# GC.net
KiCad netlist of a schematic drawn in EAGLE
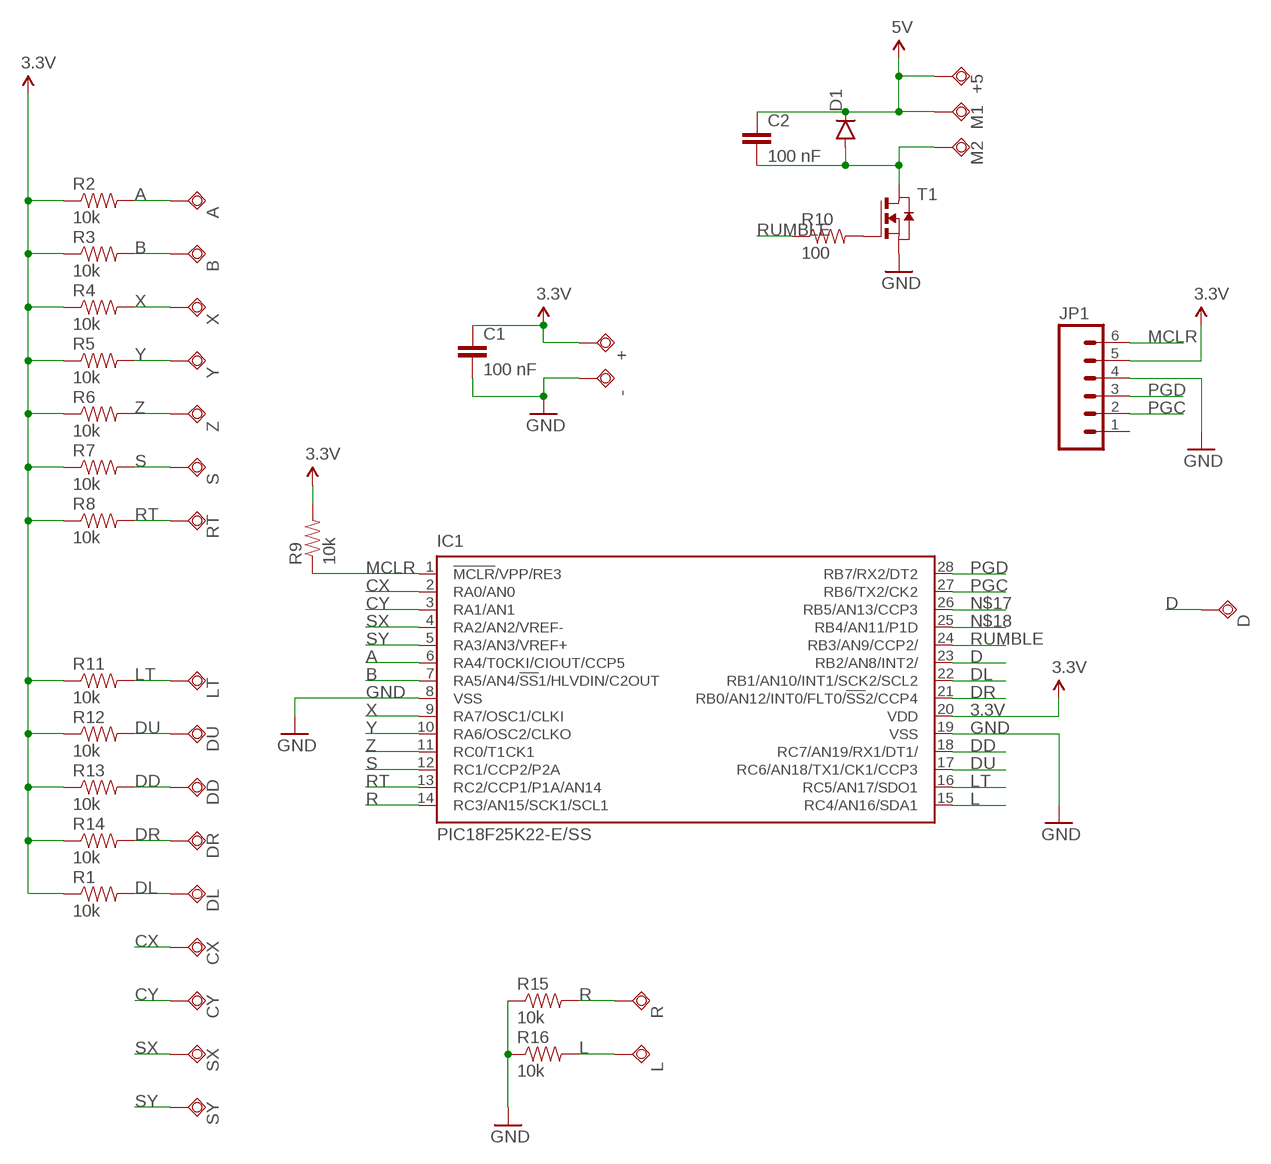
[diagram p0: schematic, sheet 1]

(export (version "E")
  (design (tool "Eeschema 10.0.6"))
  (components
    (comp (ref "+")
      (value "TPSQTP10SQ")
      (footprint "eagle-import:TP10SQ")
      (libsource (lib "eagle-import") (part "TPSQTP10SQ"))
    )
    (comp (ref "+5")
      (value "TPSQTP10SQ")
      (footprint "eagle-import:TP10SQ")
      (libsource (lib "eagle-import") (part "TPSQTP10SQ"))
    )
    (comp (ref "-")
      (value "TPSQTP10SQ")
      (footprint "eagle-import:TP10SQ")
      (libsource (lib "eagle-import") (part "TPSQTP10SQ"))
    )
    (comp (ref "A")
      (value "TPSQTP10SQ")
      (footprint "eagle-import:TP10SQ")
      (libsource (lib "eagle-import") (part "TPSQTP10SQ"))
    )
    (comp (ref "B")
      (value "TPSQTP10SQ")
      (footprint "eagle-import:TP10SQ")
      (libsource (lib "eagle-import") (part "TPSQTP10SQ"))
    )
    (comp (ref "C1")
      (value "100 nF")
      (footprint "eagle-import:0805")
      (libsource (lib "eagle-import") (part "CAP0805"))
    )
    (comp (ref "C2")
      (value "100 nF")
      (footprint "eagle-import:0805")
      (libsource (lib "eagle-import") (part "CAP0805"))
    )
    (comp (ref "CX")
      (value "TPSQTP10SQ")
      (footprint "eagle-import:TP10SQ")
      (libsource (lib "eagle-import") (part "TPSQTP10SQ"))
    )
    (comp (ref "CY")
      (value "TPSQTP10SQ")
      (footprint "eagle-import:TP10SQ")
      (libsource (lib "eagle-import") (part "TPSQTP10SQ"))
    )
    (comp (ref "D")
      (value "TPSQTP10SQ")
      (footprint "eagle-import:TP10SQ")
      (libsource (lib "eagle-import") (part "TPSQTP10SQ"))
    )
    (comp (ref "D1")
      (value "DIODEBAS16")
      (footprint "eagle-import:SOD-323")
      (libsource (lib "eagle-import") (part "DIODEBAS16"))
    )
    (comp (ref "DD")
      (value "TPSQTP10SQ")
      (footprint "eagle-import:TP10SQ")
      (libsource (lib "eagle-import") (part "TPSQTP10SQ"))
    )
    (comp (ref "DL")
      (value "TPSQTP10SQ")
      (footprint "eagle-import:TP10SQ")
      (libsource (lib "eagle-import") (part "TPSQTP10SQ"))
    )
    (comp (ref "DR")
      (value "TPSQTP10SQ")
      (footprint "eagle-import:TP10SQ")
      (libsource (lib "eagle-import") (part "TPSQTP10SQ"))
    )
    (comp (ref "DU")
      (value "TPSQTP10SQ")
      (footprint "eagle-import:TP10SQ")
      (libsource (lib "eagle-import") (part "TPSQTP10SQ"))
    )
    (comp (ref "IC1")
      (value "PIC18F25K22-E/SS")
      (footprint "eagle-import:SSOP28")
      (libsource (lib "eagle-import") (part "PIC18F25K22/SS-E"))
    )
    (comp (ref "JP1")
      (value "M06SILK_FEMALE_PTH")
      (footprint "eagle-import:1X06")
      (libsource (lib "eagle-import") (part "M06SILK_FEMALE_PTH"))
    )
    (comp (ref "L")
      (value "TPSQTP10SQ")
      (footprint "eagle-import:TP10SQ")
      (libsource (lib "eagle-import") (part "TPSQTP10SQ"))
    )
    (comp (ref "LT")
      (value "TPSQTP10SQ")
      (footprint "eagle-import:TP10SQ")
      (libsource (lib "eagle-import") (part "TPSQTP10SQ"))
    )
    (comp (ref "M1")
      (value "TPSQTP10SQ")
      (footprint "eagle-import:TP10SQ")
      (libsource (lib "eagle-import") (part "TPSQTP10SQ"))
    )
    (comp (ref "M2")
      (value "TPSQTP10SQ")
      (footprint "eagle-import:TP10SQ")
      (libsource (lib "eagle-import") (part "TPSQTP10SQ"))
    )
    (comp (ref "R")
      (value "TPSQTP10SQ")
      (footprint "eagle-import:TP10SQ")
      (libsource (lib "eagle-import") (part "TPSQTP10SQ"))
    )
    (comp (ref "R1")
      (value "10k")
      (footprint "eagle-import:0805")
      (libsource (lib "eagle-import") (part "RESISTOR0805-RES"))
    )
    (comp (ref "R2")
      (value "10k")
      (footprint "eagle-import:0805")
      (libsource (lib "eagle-import") (part "RESISTOR0805-RES"))
    )
    (comp (ref "R3")
      (value "10k")
      (footprint "eagle-import:0805")
      (libsource (lib "eagle-import") (part "RESISTOR0805-RES"))
    )
    (comp (ref "R4")
      (value "10k")
      (footprint "eagle-import:0805")
      (libsource (lib "eagle-import") (part "RESISTOR0805-RES"))
    )
    (comp (ref "R5")
      (value "10k")
      (footprint "eagle-import:0805")
      (libsource (lib "eagle-import") (part "RESISTOR0805-RES"))
    )
    (comp (ref "R6")
      (value "10k")
      (footprint "eagle-import:0805")
      (libsource (lib "eagle-import") (part "RESISTOR0805-RES"))
    )
    (comp (ref "R7")
      (value "10k")
      (footprint "eagle-import:0805")
      (libsource (lib "eagle-import") (part "RESISTOR0805-RES"))
    )
    (comp (ref "R8")
      (value "10k")
      (footprint "eagle-import:0805")
      (libsource (lib "eagle-import") (part "RESISTOR0805-RES"))
    )
    (comp (ref "R9")
      (value "10k")
      (footprint "eagle-import:0805")
      (libsource (lib "eagle-import") (part "RESISTOR0805-RES"))
    )
    (comp (ref "R10")
      (value "100")
      (footprint "eagle-import:0805")
      (libsource (lib "eagle-import") (part "RESISTOR0805-RES"))
    )
    (comp (ref "R11")
      (value "10k")
      (footprint "eagle-import:0805")
      (libsource (lib "eagle-import") (part "RESISTOR0805-RES"))
    )
    (comp (ref "R12")
      (value "10k")
      (footprint "eagle-import:0805")
      (libsource (lib "eagle-import") (part "RESISTOR0805-RES"))
    )
    (comp (ref "R13")
      (value "10k")
      (footprint "eagle-import:0805")
      (libsource (lib "eagle-import") (part "RESISTOR0805-RES"))
    )
    (comp (ref "R14")
      (value "10k")
      (footprint "eagle-import:0805")
      (libsource (lib "eagle-import") (part "RESISTOR0805-RES"))
    )
    (comp (ref "R15")
      (value "10k")
      (footprint "eagle-import:0805")
      (libsource (lib "eagle-import") (part "RESISTOR0805-RES"))
    )
    (comp (ref "R16")
      (value "10k")
      (footprint "eagle-import:0805")
      (libsource (lib "eagle-import") (part "RESISTOR0805-RES"))
    )
    (comp (ref "RT")
      (value "TPSQTP10SQ")
      (footprint "eagle-import:TP10SQ")
      (libsource (lib "eagle-import") (part "TPSQTP10SQ"))
    )
    (comp (ref "S")
      (value "TPSQTP10SQ")
      (footprint "eagle-import:TP10SQ")
      (libsource (lib "eagle-import") (part "TPSQTP10SQ"))
    )
    (comp (ref "SX")
      (value "TPSQTP10SQ")
      (footprint "eagle-import:TP10SQ")
      (libsource (lib "eagle-import") (part "TPSQTP10SQ"))
    )
    (comp (ref "SY")
      (value "TPSQTP10SQ")
      (footprint "eagle-import:TP10SQ")
      (libsource (lib "eagle-import") (part "TPSQTP10SQ"))
    )
    (comp (ref "T1")
      (value "NMOSSOT23")
      (footprint "eagle-import:SOT-23")
      (libsource (lib "eagle-import") (part "NMOSSOT23"))
    )
    (comp (ref "X")
      (value "TPSQTP10SQ")
      (footprint "eagle-import:TP10SQ")
      (libsource (lib "eagle-import") (part "TPSQTP10SQ"))
    )
    (comp (ref "Y")
      (value "TPSQTP10SQ")
      (footprint "eagle-import:TP10SQ")
      (libsource (lib "eagle-import") (part "TPSQTP10SQ"))
    )
    (comp (ref "Z")
      (value "TPSQTP10SQ")
      (footprint "eagle-import:TP10SQ")
      (libsource (lib "eagle-import") (part "TPSQTP10SQ"))
    )
  )
  (nets
    (net (code "1") (name "/A") (class "Default")
      (node (ref "A") (pin "TP") (pinfunction "TP_TP") (pintype "input"))
      (node (ref "IC1") (pin "6") (pinfunction "RA4/T0CKI/CIOUT/CCP5_6") (pintype "bidirectional"))
      (node (ref "R2") (pin "2") (pinfunction "2_2") (pintype "passive"))
    )
    (net (code "2") (name "/B") (class "Default")
      (node (ref "B") (pin "TP") (pinfunction "TP_TP") (pintype "input"))
      (node (ref "IC1") (pin "7") (pinfunction "RA5/AN4/~{SS}1/HLVDIN/C2OUT_7") (pintype "bidirectional"))
      (node (ref "R3") (pin "2") (pinfunction "2_2") (pintype "passive"))
    )
    (net (code "3") (name "/CX") (class "Default")
      (node (ref "CX") (pin "TP") (pinfunction "TP_TP") (pintype "input"))
      (node (ref "IC1") (pin "2") (pinfunction "RA0/AN0_2") (pintype "bidirectional"))
    )
    (net (code "4") (name "/CY") (class "Default")
      (node (ref "CY") (pin "TP") (pinfunction "TP_TP") (pintype "input"))
      (node (ref "IC1") (pin "3") (pinfunction "RA1/AN1_3") (pintype "bidirectional"))
    )
    (net (code "5") (name "/D") (class "Default")
      (node (ref "D") (pin "TP") (pinfunction "TP_TP") (pintype "input"))
      (node (ref "IC1") (pin "23") (pinfunction "RB2/AN8/INT2/_23") (pintype "bidirectional"))
    )
    (net (code "6") (name "/DD") (class "Default")
      (node (ref "DD") (pin "TP") (pinfunction "TP_TP") (pintype "input"))
      (node (ref "IC1") (pin "18") (pinfunction "RC7/AN19/RX1/DT1/_18") (pintype "bidirectional"))
      (node (ref "R13") (pin "2") (pinfunction "2_2") (pintype "passive"))
    )
    (net (code "7") (name "/DL") (class "Default")
      (node (ref "DL") (pin "TP") (pinfunction "TP_TP") (pintype "input"))
      (node (ref "IC1") (pin "22") (pinfunction "RB1/AN10/INT1/SCK2/SCL2_22") (pintype "bidirectional"))
      (node (ref "R1") (pin "2") (pinfunction "2_2") (pintype "passive"))
    )
    (net (code "8") (name "/DR") (class "Default")
      (node (ref "DR") (pin "TP") (pinfunction "TP_TP") (pintype "input"))
      (node (ref "IC1") (pin "21") (pinfunction "RB0/AN12/INT0/FLT0/~{SS}2/CCP4_21") (pintype "bidirectional"))
      (node (ref "R14") (pin "2") (pinfunction "2_2") (pintype "passive"))
    )
    (net (code "9") (name "/DU") (class "Default")
      (node (ref "DU") (pin "TP") (pinfunction "TP_TP") (pintype "input"))
      (node (ref "IC1") (pin "17") (pinfunction "RC6/AN18/TX1/CK1/CCP3_17") (pintype "bidirectional"))
      (node (ref "R12") (pin "2") (pinfunction "2_2") (pintype "passive"))
    )
    (net (code "10") (name "/L") (class "Default")
      (node (ref "IC1") (pin "15") (pinfunction "RC4/AN16/SDA1_15") (pintype "bidirectional"))
      (node (ref "L") (pin "TP") (pinfunction "TP_TP") (pintype "input"))
      (node (ref "R16") (pin "2") (pinfunction "2_2") (pintype "passive"))
    )
    (net (code "11") (name "/LT") (class "Default")
      (node (ref "IC1") (pin "16") (pinfunction "RC5/AN17/SDO1_16") (pintype "bidirectional"))
      (node (ref "LT") (pin "TP") (pinfunction "TP_TP") (pintype "input"))
      (node (ref "R11") (pin "2") (pinfunction "2_2") (pintype "passive"))
    )
    (net (code "12") (name "/MCLR") (class "Default")
      (node (ref "IC1") (pin "1") (pinfunction "~{MCLR}/VPP/RE3_1") (pintype "input"))
      (node (ref "JP1") (pin "6") (pinfunction "6_6") (pintype "passive"))
      (node (ref "R9") (pin "1") (pinfunction "1_1") (pintype "passive"))
    )
    (net (code "13") (name "/N$17") (class "Default")
      (node (ref "IC1") (pin "26") (pinfunction "RB5/AN13/CCP3_26") (pintype "bidirectional"))
    )
    (net (code "14") (name "/N$18") (class "Default")
      (node (ref "IC1") (pin "25") (pinfunction "RB4/AN11/P1D_25") (pintype "bidirectional"))
    )
    (net (code "15") (name "/PGC") (class "Default")
      (node (ref "IC1") (pin "27") (pinfunction "RB6/TX2/CK2_27") (pintype "bidirectional"))
      (node (ref "JP1") (pin "2") (pinfunction "2_2") (pintype "passive"))
    )
    (net (code "16") (name "/PGD") (class "Default")
      (node (ref "IC1") (pin "28") (pinfunction "RB7/RX2/DT2_28") (pintype "bidirectional"))
      (node (ref "JP1") (pin "3") (pinfunction "3_3") (pintype "passive"))
    )
    (net (code "17") (name "/R") (class "Default")
      (node (ref "IC1") (pin "14") (pinfunction "RC3/AN15/SCK1/SCL1_14") (pintype "bidirectional"))
      (node (ref "R") (pin "TP") (pinfunction "TP_TP") (pintype "input"))
      (node (ref "R15") (pin "2") (pinfunction "2_2") (pintype "passive"))
    )
    (net (code "18") (name "/RT") (class "Default")
      (node (ref "IC1") (pin "13") (pinfunction "RC2/CCP1/P1A/AN14_13") (pintype "bidirectional"))
      (node (ref "R8") (pin "2") (pinfunction "2_2") (pintype "passive"))
      (node (ref "RT") (pin "TP") (pinfunction "TP_TP") (pintype "input"))
    )
    (net (code "19") (name "/RUMBLE") (class "Default")
      (node (ref "IC1") (pin "24") (pinfunction "RB3/AN9/CCP2/_24") (pintype "bidirectional"))
      (node (ref "R10") (pin "1") (pinfunction "1_1") (pintype "passive"))
    )
    (net (code "20") (name "/S") (class "Default")
      (node (ref "IC1") (pin "12") (pinfunction "RC1/CCP2/P2A_12") (pintype "bidirectional"))
      (node (ref "R7") (pin "2") (pinfunction "2_2") (pintype "passive"))
      (node (ref "S") (pin "TP") (pinfunction "TP_TP") (pintype "input"))
    )
    (net (code "21") (name "/SX") (class "Default")
      (node (ref "IC1") (pin "4") (pinfunction "RA2/AN2/VREF-_4") (pintype "bidirectional"))
      (node (ref "SX") (pin "TP") (pinfunction "TP_TP") (pintype "input"))
    )
    (net (code "22") (name "/SY") (class "Default")
      (node (ref "IC1") (pin "5") (pinfunction "RA3/AN3/VREF+_5") (pintype "bidirectional"))
      (node (ref "SY") (pin "TP") (pinfunction "TP_TP") (pintype "input"))
    )
    (net (code "23") (name "/X") (class "Default")
      (node (ref "IC1") (pin "9") (pinfunction "RA7/OSC1/CLKI_9") (pintype "input"))
      (node (ref "R4") (pin "2") (pinfunction "2_2") (pintype "passive"))
      (node (ref "X") (pin "TP") (pinfunction "TP_TP") (pintype "input"))
    )
    (net (code "24") (name "/Y") (class "Default")
      (node (ref "IC1") (pin "10") (pinfunction "RA6/OSC2/CLKO_10") (pintype "output"))
      (node (ref "R5") (pin "2") (pinfunction "2_2") (pintype "passive"))
      (node (ref "Y") (pin "TP") (pinfunction "TP_TP") (pintype "input"))
    )
    (net (code "25") (name "/Z") (class "Default")
      (node (ref "IC1") (pin "11") (pinfunction "RC0/T1CK1_11") (pintype "bidirectional"))
      (node (ref "R6") (pin "2") (pinfunction "2_2") (pintype "passive"))
      (node (ref "Z") (pin "TP") (pinfunction "TP_TP") (pintype "input"))
    )
    (net (code "26") (name "3.3V") (class "Default")
      (node (ref "+") (pin "TP") (pinfunction "TP_TP") (pintype "input"))
      (node (ref "C1") (pin "1") (pinfunction "1_1") (pintype "passive"))
      (node (ref "IC1") (pin "20") (pinfunction "VDD_20") (pintype "power_in"))
      (node (ref "JP1") (pin "5") (pinfunction "5_5") (pintype "passive"))
      (node (ref "R1") (pin "1") (pinfunction "1_1") (pintype "passive"))
      (node (ref "R11") (pin "1") (pinfunction "1_1") (pintype "passive"))
      (node (ref "R12") (pin "1") (pinfunction "1_1") (pintype "passive"))
      (node (ref "R13") (pin "1") (pinfunction "1_1") (pintype "passive"))
      (node (ref "R14") (pin "1") (pinfunction "1_1") (pintype "passive"))
      (node (ref "R2") (pin "1") (pinfunction "1_1") (pintype "passive"))
      (node (ref "R3") (pin "1") (pinfunction "1_1") (pintype "passive"))
      (node (ref "R4") (pin "1") (pinfunction "1_1") (pintype "passive"))
      (node (ref "R5") (pin "1") (pinfunction "1_1") (pintype "passive"))
      (node (ref "R6") (pin "1") (pinfunction "1_1") (pintype "passive"))
      (node (ref "R7") (pin "1") (pinfunction "1_1") (pintype "passive"))
      (node (ref "R8") (pin "1") (pinfunction "1_1") (pintype "passive"))
      (node (ref "R9") (pin "2") (pinfunction "2_2") (pintype "passive"))
    )
    (net (code "27") (name "5V") (class "Default")
      (node (ref "+5") (pin "TP") (pinfunction "TP_TP") (pintype "input"))
      (node (ref "C2") (pin "1") (pinfunction "1_1") (pintype "passive"))
      (node (ref "D1") (pin "C") (pinfunction "C_C") (pintype "passive"))
      (node (ref "M1") (pin "TP") (pinfunction "TP_TP") (pintype "input"))
    )
    (net (code "28") (name "GND") (class "Default")
      (node (ref "-") (pin "TP") (pinfunction "TP_TP") (pintype "input"))
      (node (ref "C1") (pin "2") (pinfunction "2_2") (pintype "passive"))
      (node (ref "IC1") (pin "19") (pinfunction "VSS_19") (pintype "power_in"))
      (node (ref "IC1") (pin "8") (pinfunction "VSS_8") (pintype "power_in"))
      (node (ref "JP1") (pin "4") (pinfunction "4_4") (pintype "passive"))
      (node (ref "R15") (pin "1") (pinfunction "1_1") (pintype "passive"))
      (node (ref "R16") (pin "1") (pinfunction "1_1") (pintype "passive"))
      (node (ref "T1") (pin "2") (pinfunction "S_2") (pintype "passive"))
    )
    (net (code "29") (name "Net-(T1-D)") (class "Default")
      (node (ref "C2") (pin "2") (pinfunction "2_2") (pintype "passive"))
      (node (ref "D1") (pin "A") (pinfunction "A_A") (pintype "passive"))
      (node (ref "M2") (pin "TP") (pinfunction "TP_TP") (pintype "input"))
      (node (ref "T1") (pin "1") (pinfunction "D_1") (pintype "passive"))
    )
    (net (code "30") (name "Net-(T1-G)") (class "Default")
      (node (ref "R10") (pin "2") (pinfunction "2_2") (pintype "passive"))
      (node (ref "T1") (pin "3") (pinfunction "G_3") (pintype "passive"))
    )
    (net (code "31") (name "unconnected-(JP1-Pad1)") (class "Default")
      (node (ref "JP1") (pin "1") (pinfunction "1_1") (pintype "passive"))
    )
  )
)
